# FabTouche.net
KiCad netlist of a schematic drawn in EAGLE
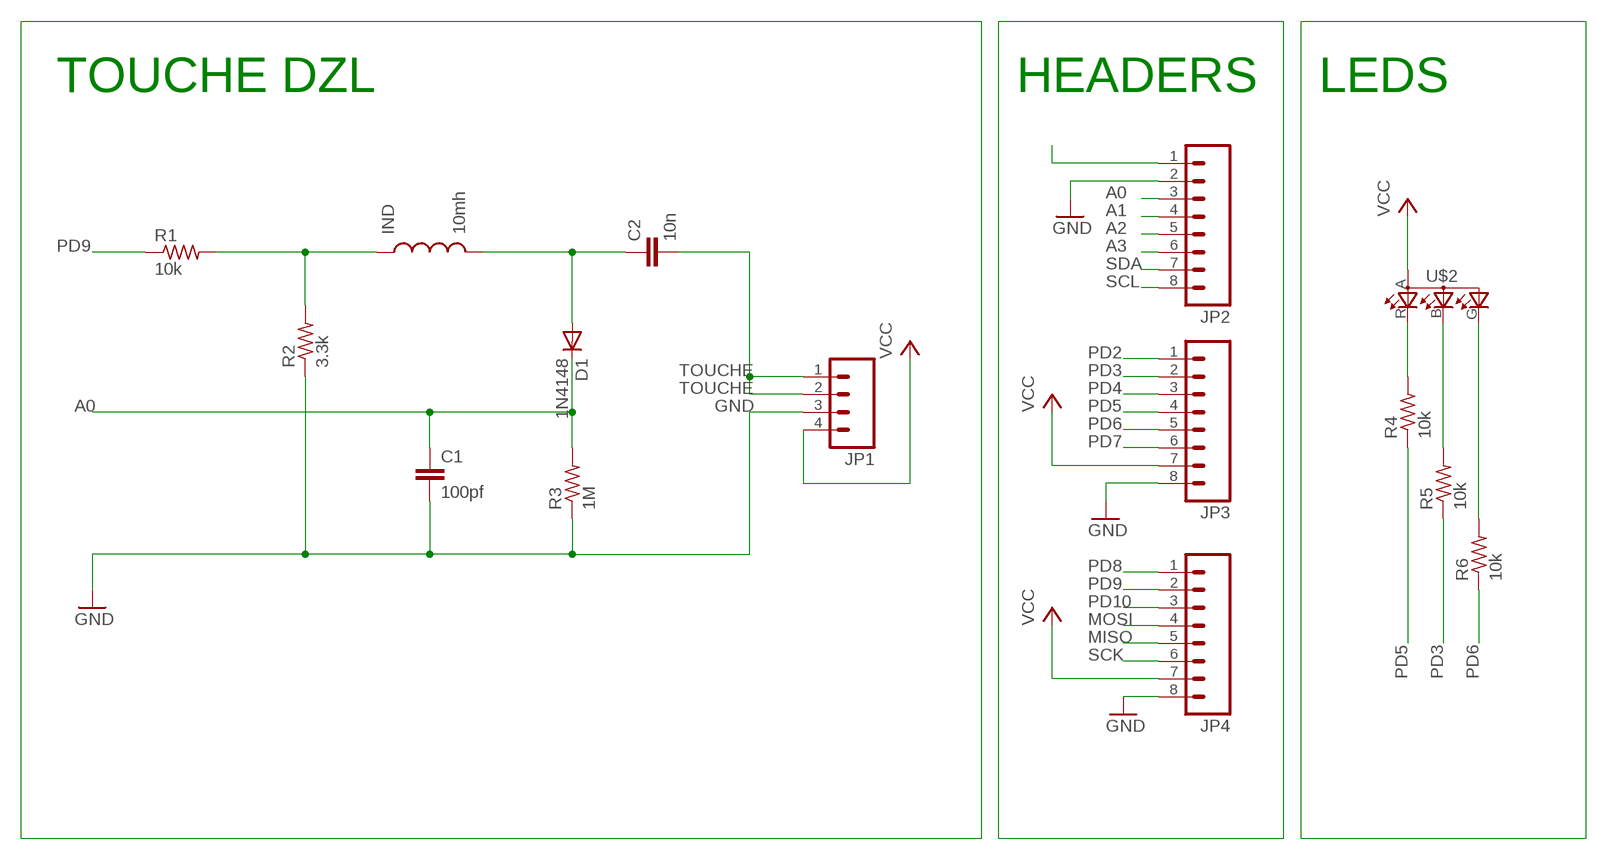
[diagram p0: schematic, sheet 1]

(export (version "E")
  (design (tool "Eeschema 10.0.6"))
  (components
    (comp (ref "C1")
      (value "100pf")
      (footprint "eagle-import:1206")
      (libsource (lib "eagle-import") (part "CAP1206"))
    )
    (comp (ref "C2")
      (value "10n")
      (footprint "eagle-import:1206")
      (libsource (lib "eagle-import") (part "CAP1206"))
    )
    (comp (ref "D1")
      (value "1N4148")
      (footprint "eagle-import:SOD123")
      (libsource (lib "eagle-import") (part "DIODESOD123"))
    )
    (comp (ref "IND")
      (value "10mh")
      (footprint "eagle-import:CDRH3D28")
      (libsource (lib "eagle-import") (part "INDUCTOR"))
    )
    (comp (ref "JP1")
      (value "M04PTH")
      (footprint "eagle-import:1X04")
      (libsource (lib "eagle-import") (part "M04PTH"))
    )
    (comp (ref "JP2")
      (value "M08")
      (footprint "eagle-import:1X08")
      (libsource (lib "eagle-import") (part "M08"))
    )
    (comp (ref "JP3")
      (value "M08")
      (footprint "eagle-import:1X08")
      (libsource (lib "eagle-import") (part "M08"))
    )
    (comp (ref "JP4")
      (value "M08")
      (footprint "eagle-import:1X08")
      (libsource (lib "eagle-import") (part "M08"))
    )
    (comp (ref "R1")
      (value "10k")
      (footprint "eagle-import:1206")
      (libsource (lib "eagle-import") (part "RESISTOR1206"))
    )
    (comp (ref "R2")
      (value "3.3k")
      (footprint "eagle-import:1206")
      (libsource (lib "eagle-import") (part "RESISTOR1206"))
    )
    (comp (ref "R3")
      (value "1M")
      (footprint "eagle-import:1206")
      (libsource (lib "eagle-import") (part "RESISTOR1206"))
    )
    (comp (ref "R4")
      (value "10k")
      (footprint "eagle-import:1206")
      (libsource (lib "eagle-import") (part "RESISTOR1206"))
    )
    (comp (ref "R5")
      (value "10k")
      (footprint "eagle-import:1206")
      (libsource (lib "eagle-import") (part "RESISTOR1206"))
    )
    (comp (ref "R6")
      (value "10k")
      (footprint "eagle-import:1206")
      (libsource (lib "eagle-import") (part "RESISTOR1206"))
    )
    (comp (ref "U$2")
      (value "LEDRGBOLD")
      (footprint "eagle-import:P-LCC-4-3")
      (libsource (lib "eagle-import") (part "LEDRGBOLD"))
    )
  )
  (nets
    (net (code "1") (name "/A0") (class "Default")
      (node (ref "C1") (pin "1") (pinfunction "1_1") (pintype "passive"))
      (node (ref "D1") (pin "CATHODE") (pinfunction "C_CATHODE") (pintype "passive"))
      (node (ref "JP2") (pin "3") (pinfunction "3_3") (pintype "passive"))
      (node (ref "R3") (pin "2") (pinfunction "2_2") (pintype "passive"))
    )
    (net (code "2") (name "/A1") (class "Default")
      (node (ref "JP2") (pin "4") (pinfunction "4_4") (pintype "passive"))
    )
    (net (code "3") (name "/A2") (class "Default")
      (node (ref "JP2") (pin "5") (pinfunction "5_5") (pintype "passive"))
    )
    (net (code "4") (name "/A3") (class "Default")
      (node (ref "JP2") (pin "6") (pinfunction "6_6") (pintype "passive"))
    )
    (net (code "5") (name "/MISO") (class "Default")
      (node (ref "JP4") (pin "5") (pinfunction "5_5") (pintype "passive"))
    )
    (net (code "6") (name "/MOSI") (class "Default")
      (node (ref "JP4") (pin "4") (pinfunction "4_4") (pintype "passive"))
    )
    (net (code "7") (name "/PD2") (class "Default")
      (node (ref "JP3") (pin "1") (pinfunction "1_1") (pintype "passive"))
    )
    (net (code "8") (name "/PD3") (class "Default")
      (node (ref "JP3") (pin "2") (pinfunction "2_2") (pintype "passive"))
      (node (ref "R5") (pin "1") (pinfunction "1_1") (pintype "passive"))
    )
    (net (code "9") (name "/PD4") (class "Default")
      (node (ref "JP3") (pin "3") (pinfunction "3_3") (pintype "passive"))
    )
    (net (code "10") (name "/PD5") (class "Default")
      (node (ref "JP3") (pin "4") (pinfunction "4_4") (pintype "passive"))
      (node (ref "R4") (pin "1") (pinfunction "1_1") (pintype "passive"))
    )
    (net (code "11") (name "/PD6") (class "Default")
      (node (ref "JP3") (pin "5") (pinfunction "5_5") (pintype "passive"))
      (node (ref "R6") (pin "1") (pinfunction "1_1") (pintype "passive"))
    )
    (net (code "12") (name "/PD7") (class "Default")
      (node (ref "JP3") (pin "6") (pinfunction "6_6") (pintype "passive"))
    )
    (net (code "13") (name "/PD8") (class "Default")
      (node (ref "JP4") (pin "1") (pinfunction "1_1") (pintype "passive"))
    )
    (net (code "14") (name "/PD9") (class "Default")
      (node (ref "JP4") (pin "2") (pinfunction "2_2") (pintype "passive"))
      (node (ref "R1") (pin "1") (pinfunction "1_1") (pintype "passive"))
    )
    (net (code "15") (name "/PD10") (class "Default")
      (node (ref "JP4") (pin "3") (pinfunction "3_3") (pintype "passive"))
    )
    (net (code "16") (name "/SCK") (class "Default")
      (node (ref "JP4") (pin "6") (pinfunction "6_6") (pintype "passive"))
    )
    (net (code "17") (name "/SCL") (class "Default")
      (node (ref "JP2") (pin "8") (pinfunction "8_8") (pintype "passive"))
    )
    (net (code "18") (name "/SDA") (class "Default")
      (node (ref "JP2") (pin "7") (pinfunction "7_7") (pintype "passive"))
    )
    (net (code "19") (name "/TOUCHE") (class "Default")
      (node (ref "C2") (pin "2") (pinfunction "2_2") (pintype "passive"))
      (node (ref "JP1") (pin "1") (pinfunction "1_1") (pintype "passive"))
      (node (ref "JP1") (pin "2") (pinfunction "2_2") (pintype "passive"))
    )
    (net (code "20") (name "GND") (class "Default")
      (node (ref "C1") (pin "2") (pinfunction "2_2") (pintype "passive"))
      (node (ref "JP1") (pin "3") (pinfunction "3_3") (pintype "passive"))
      (node (ref "JP2") (pin "2") (pinfunction "2_2") (pintype "passive"))
      (node (ref "JP3") (pin "8") (pinfunction "8_8") (pintype "passive"))
      (node (ref "JP4") (pin "8") (pinfunction "8_8") (pintype "passive"))
      (node (ref "R2") (pin "1") (pinfunction "1_1") (pintype "passive"))
      (node (ref "R3") (pin "1") (pinfunction "1_1") (pintype "passive"))
    )
    (net (code "21") (name "Net-(D1-A)") (class "Default")
      (node (ref "C2") (pin "1") (pinfunction "1_1") (pintype "passive"))
      (node (ref "D1") (pin "ANODE") (pinfunction "A_ANODE") (pintype "passive"))
      (node (ref "IND") (pin "2") (pinfunction "2_2") (pintype "passive"))
    )
    (net (code "22") (name "Net-(IND-Pad1)") (class "Default")
      (node (ref "IND") (pin "1") (pinfunction "1_1") (pintype "passive"))
      (node (ref "R1") (pin "2") (pinfunction "2_2") (pintype "passive"))
      (node (ref "R2") (pin "2") (pinfunction "2_2") (pintype "passive"))
    )
    (net (code "23") (name "Net-(U$2-CBLUE)") (class "Default")
      (node (ref "R5") (pin "2") (pinfunction "2_2") (pintype "passive"))
      (node (ref "U$2") (pin "B") (pinfunction "CBLUE_B") (pintype "passive"))
    )
    (net (code "24") (name "Net-(U$2-CGREEN)") (class "Default")
      (node (ref "R6") (pin "2") (pinfunction "2_2") (pintype "passive"))
      (node (ref "U$2") (pin "G") (pinfunction "CGREEN_G") (pintype "passive"))
    )
    (net (code "25") (name "Net-(U$2-CRED)") (class "Default")
      (node (ref "R4") (pin "2") (pinfunction "2_2") (pintype "passive"))
      (node (ref "U$2") (pin "R") (pinfunction "CRED_R") (pintype "passive"))
    )
    (net (code "26") (name "VCC") (class "Default")
      (node (ref "JP1") (pin "4") (pinfunction "4_4") (pintype "passive"))
      (node (ref "JP3") (pin "7") (pinfunction "7_7") (pintype "passive"))
      (node (ref "JP4") (pin "7") (pinfunction "7_7") (pintype "passive"))
      (node (ref "U$2") (pin "A") (pinfunction "A2_A") (pintype "passive"))
    )
    (net (code "27") (name "unconnected-(JP2-Pad1)") (class "Default")
      (node (ref "JP2") (pin "1") (pinfunction "1_1") (pintype "passive"))
    )
  )
)
